# TMR01.net
KiCad netlist of a schematic drawn in EAGLE
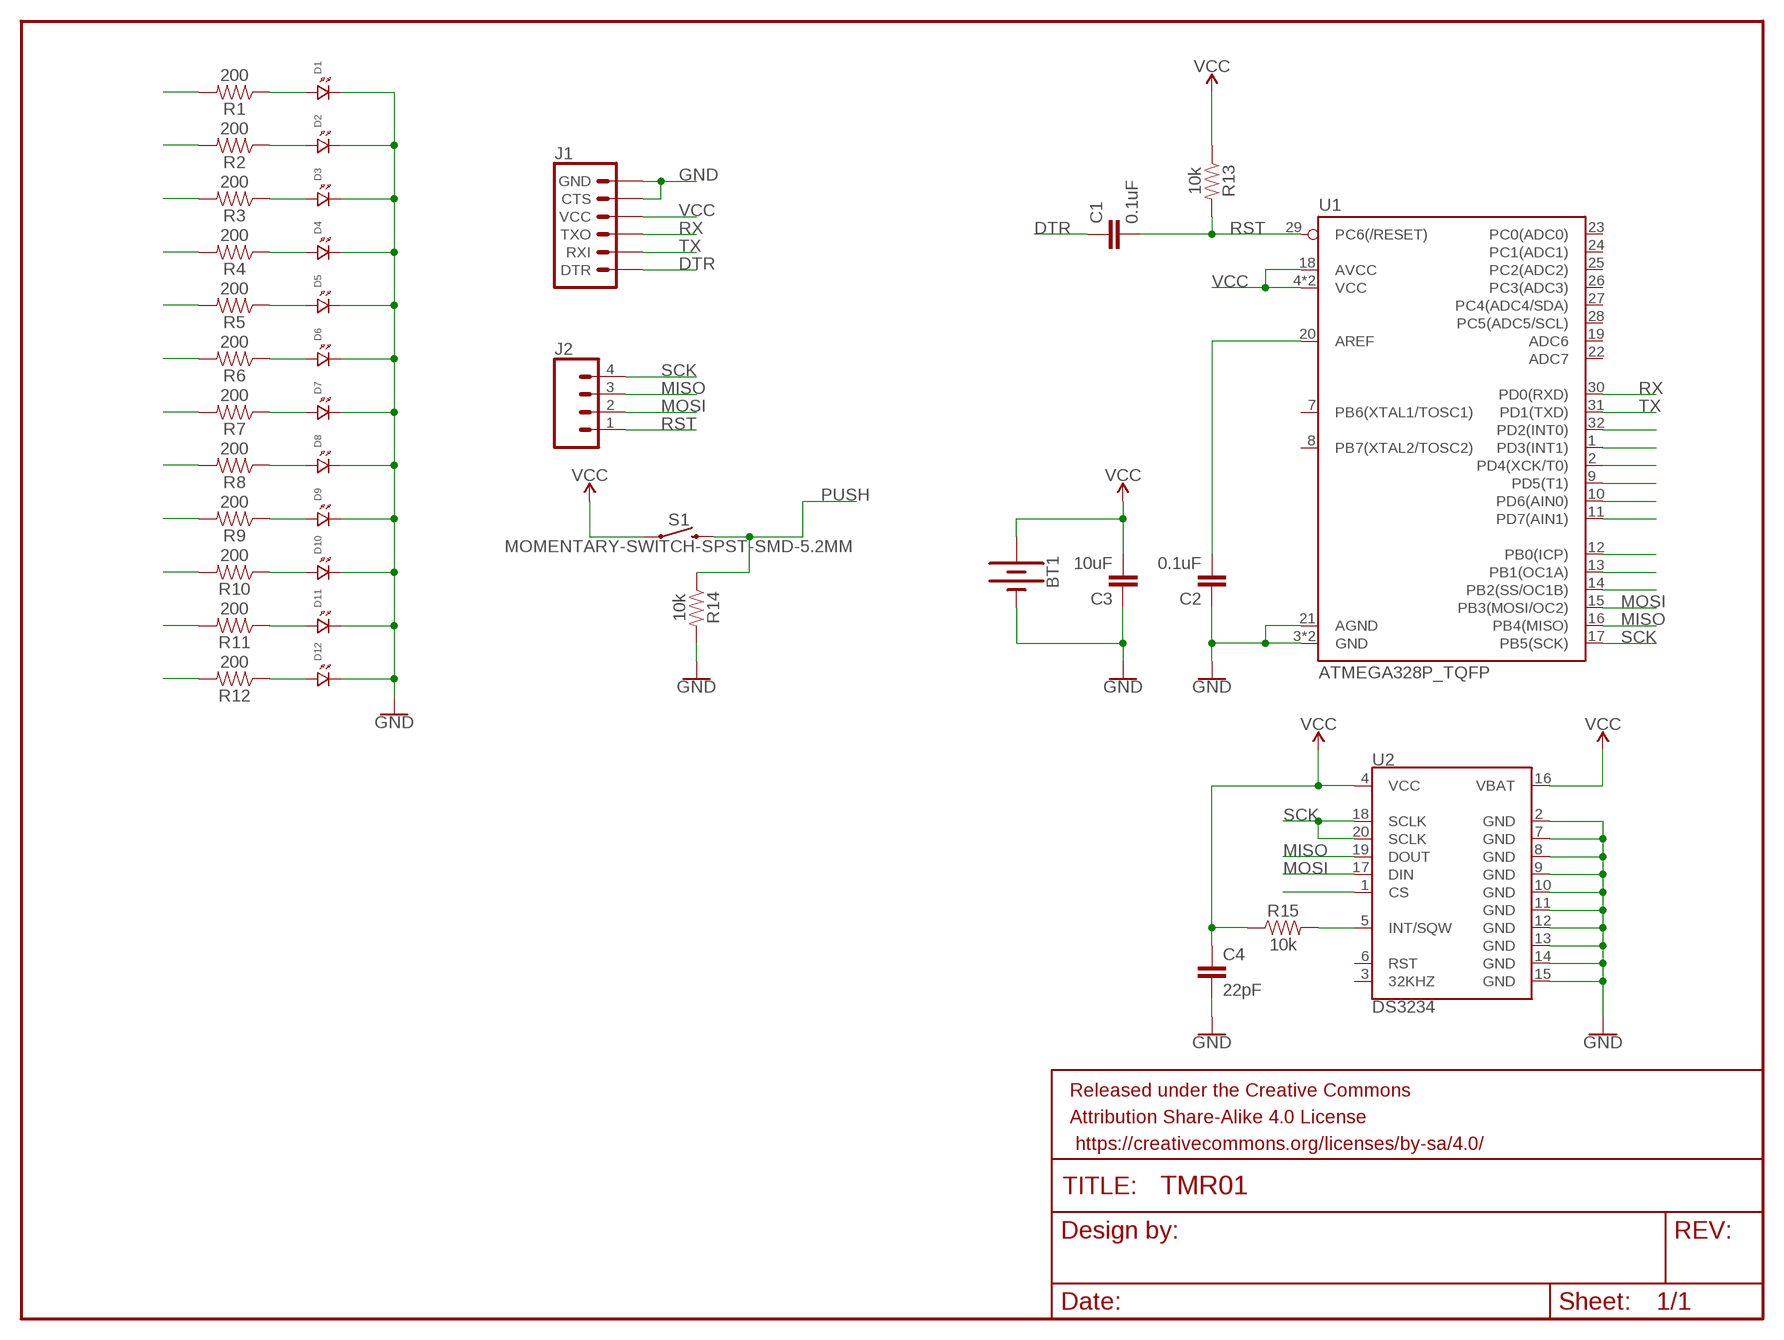
[diagram p0: schematic, sheet 1]

(export (version "E")
  (design (tool "Eeschema 10.0.6"))
  (components
    (comp (ref "BT1")
      (value "BATTERY-20MM_SMD_4LEGS")
      (footprint "eagle-import:BATTCON_20MM_4LEGS")
      (libsource (lib "eagle-import") (part "BATTERY-20MM_SMD_4LEGS"))
    )
    (comp (ref "C1")
      (value "0.1uF")
      (footprint "eagle-import:0402")
      (libsource (lib "eagle-import") (part "0.1UF-0402-16V-10%"))
    )
    (comp (ref "C2")
      (value "0.1uF")
      (footprint "eagle-import:0402")
      (libsource (lib "eagle-import") (part "0.1UF-0402-16V-10%"))
    )
    (comp (ref "C3")
      (value "10uF")
      (footprint "eagle-import:0805")
      (libsource (lib "eagle-import") (part "10UF-0805-10V-10%"))
    )
    (comp (ref "C4")
      (value "22pF")
      (footprint "eagle-import:0402")
      (libsource (lib "eagle-import") (part "CAP_0402"))
    )
    (comp (ref "D1")
      (value "LED.0402")
      (footprint "eagle-import:0402.LED")
      (libsource (lib "eagle-import") (part "LED.0402"))
    )
    (comp (ref "D2")
      (value "LED.0402")
      (footprint "eagle-import:0402.LED")
      (libsource (lib "eagle-import") (part "LED.0402"))
    )
    (comp (ref "D3")
      (value "LED.0402")
      (footprint "eagle-import:0402.LED")
      (libsource (lib "eagle-import") (part "LED.0402"))
    )
    (comp (ref "D4")
      (value "LED.0402")
      (footprint "eagle-import:0402.LED")
      (libsource (lib "eagle-import") (part "LED.0402"))
    )
    (comp (ref "D5")
      (value "LED.0402")
      (footprint "eagle-import:0402.LED")
      (libsource (lib "eagle-import") (part "LED.0402"))
    )
    (comp (ref "D6")
      (value "LED.0402")
      (footprint "eagle-import:0402.LED")
      (libsource (lib "eagle-import") (part "LED.0402"))
    )
    (comp (ref "D7")
      (value "LED.0402")
      (footprint "eagle-import:0402.LED")
      (libsource (lib "eagle-import") (part "LED.0402"))
    )
    (comp (ref "D8")
      (value "LED.0402")
      (footprint "eagle-import:0402.LED")
      (libsource (lib "eagle-import") (part "LED.0402"))
    )
    (comp (ref "D9")
      (value "LED.0402")
      (footprint "eagle-import:0402.LED")
      (libsource (lib "eagle-import") (part "LED.0402"))
    )
    (comp (ref "D10")
      (value "LED.0402")
      (footprint "eagle-import:0402.LED")
      (libsource (lib "eagle-import") (part "LED.0402"))
    )
    (comp (ref "D11")
      (value "LED.0402")
      (footprint "eagle-import:0402.LED")
      (libsource (lib "eagle-import") (part "LED.0402"))
    )
    (comp (ref "D12")
      (value "LED.0402")
      (footprint "eagle-import:0402.LED")
      (libsource (lib "eagle-import") (part "LED.0402"))
    )
    (comp (ref "FRAME1")
      (value "FRAME-LETTER")
      (footprint "eagle-import:CREATIVE_COMMONS")
      (libsource (lib "eagle-import") (part "FRAME-LETTER"))
    )
    (comp (ref "J1")
      (value "6_PIN_SERIAL_TARGET")
      (footprint "eagle-import:1X06")
      (libsource (lib "eagle-import") (part "6_PIN_SERIAL_TARGET"))
    )
    (comp (ref "J2")
      (value "CONN_04")
      (footprint "eagle-import:1X04")
      (libsource (lib "eagle-import") (part "CONN_04"))
    )
    (comp (ref "R1")
      (value "200")
      (footprint "eagle-import:0402")
      (libsource (lib "eagle-import") (part "RESISTOR0402"))
    )
    (comp (ref "R2")
      (value "200")
      (footprint "eagle-import:0402")
      (libsource (lib "eagle-import") (part "RESISTOR0402"))
    )
    (comp (ref "R3")
      (value "200")
      (footprint "eagle-import:0402")
      (libsource (lib "eagle-import") (part "RESISTOR0402"))
    )
    (comp (ref "R4")
      (value "200")
      (footprint "eagle-import:0402")
      (libsource (lib "eagle-import") (part "RESISTOR0402"))
    )
    (comp (ref "R5")
      (value "200")
      (footprint "eagle-import:0402")
      (libsource (lib "eagle-import") (part "RESISTOR0402"))
    )
    (comp (ref "R6")
      (value "200")
      (footprint "eagle-import:0402")
      (libsource (lib "eagle-import") (part "RESISTOR0402"))
    )
    (comp (ref "R7")
      (value "200")
      (footprint "eagle-import:0402")
      (libsource (lib "eagle-import") (part "RESISTOR0402"))
    )
    (comp (ref "R8")
      (value "200")
      (footprint "eagle-import:0402")
      (libsource (lib "eagle-import") (part "RESISTOR0402"))
    )
    (comp (ref "R9")
      (value "200")
      (footprint "eagle-import:0402")
      (libsource (lib "eagle-import") (part "RESISTOR0402"))
    )
    (comp (ref "R10")
      (value "200")
      (footprint "eagle-import:0402")
      (libsource (lib "eagle-import") (part "RESISTOR0402"))
    )
    (comp (ref "R11")
      (value "200")
      (footprint "eagle-import:0402")
      (libsource (lib "eagle-import") (part "RESISTOR0402"))
    )
    (comp (ref "R12")
      (value "200")
      (footprint "eagle-import:0402")
      (libsource (lib "eagle-import") (part "RESISTOR0402"))
    )
    (comp (ref "R13")
      (value "10k")
      (footprint "eagle-import:0402")
      (libsource (lib "eagle-import") (part "RESISTOR0402"))
    )
    (comp (ref "R14")
      (value "10k")
      (footprint "eagle-import:0402")
      (libsource (lib "eagle-import") (part "RESISTOR0402"))
    )
    (comp (ref "R15")
      (value "10k")
      (footprint "eagle-import:0402")
      (libsource (lib "eagle-import") (part "RESISTOR0402"))
    )
    (comp (ref "S1")
      (value "MOMENTARY-SWITCH-SPST-SMD-5.2MM")
      (footprint "eagle-import:TACTILE_SWITCH_SMD_5.2MM")
      (libsource (lib "eagle-import") (part "MOMENTARY-SWITCH-SPST-SMD-5.2MM"))
    )
    (comp (ref "U1")
      (value "ATMEGA328P_TQFP")
      (footprint "eagle-import:TQFP32-08")
      (libsource (lib "eagle-import") (part "ATMEGA328P_TQFP"))
    )
    (comp (ref "U2")
      (value "DS3234")
      (footprint "eagle-import:SO20-0.3")
      (libsource (lib "eagle-import") (part "DS3234"))
    )
  )
  (nets
    (net (code "1") (name "/DTR") (class "Default")
      (node (ref "C1") (pin "1") (pinfunction "1_1") (pintype "passive"))
      (node (ref "J1") (pin "1") (pinfunction "DTR_1") (pintype "passive"))
    )
    (net (code "2") (name "/MISO") (class "Default")
      (node (ref "J2") (pin "3") (pinfunction "3_3") (pintype "passive"))
      (node (ref "U1") (pin "16") (pinfunction "PB4(MISO)_16") (pintype "bidirectional"))
      (node (ref "U2") (pin "19") (pinfunction "DOUT_19") (pintype "bidirectional"))
    )
    (net (code "3") (name "/MOSI") (class "Default")
      (node (ref "J2") (pin "2") (pinfunction "2_2") (pintype "passive"))
      (node (ref "U1") (pin "15") (pinfunction "PB3(MOSI/OC2)_15") (pintype "bidirectional"))
      (node (ref "U2") (pin "17") (pinfunction "DIN_17") (pintype "bidirectional"))
    )
    (net (code "4") (name "/PUSH") (class "Default")
      (node (ref "R14") (pin "1") (pinfunction "1_1") (pintype "passive"))
      (node (ref "S1") (pin "3") (pinfunction "2_3") (pintype "passive"))
    )
    (net (code "5") (name "/RST") (class "Default")
      (node (ref "C1") (pin "2") (pinfunction "2_2") (pintype "passive"))
      (node (ref "J2") (pin "1") (pinfunction "1_1") (pintype "passive"))
      (node (ref "R13") (pin "2") (pinfunction "2_2") (pintype "passive"))
      (node (ref "U1") (pin "29") (pinfunction "PC6(/RESET)_29") (pintype "bidirectional"))
    )
    (net (code "6") (name "/RX") (class "Default")
      (node (ref "J1") (pin "3") (pinfunction "TXO_3") (pintype "passive"))
      (node (ref "U1") (pin "30") (pinfunction "PD0(RXD)_30") (pintype "bidirectional"))
    )
    (net (code "7") (name "/SCK") (class "Default")
      (node (ref "J2") (pin "4") (pinfunction "4_4") (pintype "passive"))
      (node (ref "U1") (pin "17") (pinfunction "PB5(SCK)_17") (pintype "bidirectional"))
      (node (ref "U2") (pin "18") (pinfunction "SCLK_18") (pintype "bidirectional"))
      (node (ref "U2") (pin "20") (pinfunction "SCLK_20") (pintype "bidirectional"))
    )
    (net (code "8") (name "/TX") (class "Default")
      (node (ref "J1") (pin "2") (pinfunction "RXI_2") (pintype "passive"))
      (node (ref "U1") (pin "31") (pinfunction "PD1(TXD)_31") (pintype "bidirectional"))
    )
    (net (code "9") (name "GND") (class "Default")
      (node (ref "BT1") (pin "NEGATIVE") (pinfunction "-_NEGATIVE") (pintype "power_in"))
      (node (ref "C2") (pin "1") (pinfunction "1_1") (pintype "passive"))
      (node (ref "C3") (pin "1") (pinfunction "1_1") (pintype "passive"))
      (node (ref "C4") (pin "2") (pinfunction "2_2") (pintype "passive"))
      (node (ref "D1") (pin "P$2") (pinfunction "2_P$2") (pintype "bidirectional"))
      (node (ref "D10") (pin "P$2") (pinfunction "2_P$2") (pintype "bidirectional"))
      (node (ref "D11") (pin "P$2") (pinfunction "2_P$2") (pintype "bidirectional"))
      (node (ref "D12") (pin "P$2") (pinfunction "2_P$2") (pintype "bidirectional"))
      (node (ref "D2") (pin "P$2") (pinfunction "2_P$2") (pintype "bidirectional"))
      (node (ref "D3") (pin "P$2") (pinfunction "2_P$2") (pintype "bidirectional"))
      (node (ref "D4") (pin "P$2") (pinfunction "2_P$2") (pintype "bidirectional"))
      (node (ref "D5") (pin "P$2") (pinfunction "2_P$2") (pintype "bidirectional"))
      (node (ref "D6") (pin "P$2") (pinfunction "2_P$2") (pintype "bidirectional"))
      (node (ref "D7") (pin "P$2") (pinfunction "2_P$2") (pintype "bidirectional"))
      (node (ref "D8") (pin "P$2") (pinfunction "2_P$2") (pintype "bidirectional"))
      (node (ref "D9") (pin "P$2") (pinfunction "2_P$2") (pintype "bidirectional"))
      (node (ref "J1") (pin "5") (pinfunction "CTS_5") (pintype "passive"))
      (node (ref "J1") (pin "6") (pinfunction "GND_6") (pintype "passive"))
      (node (ref "R14") (pin "2") (pinfunction "2_2") (pintype "passive"))
      (node (ref "U1") (pin "21") (pinfunction "AGND_21") (pintype "bidirectional"))
      (node (ref "U1") (pin "3") (pinfunction "GND_3") (pintype "bidirectional"))
      (node (ref "U1") (pin "5") (pinfunction "GND_5") (pintype "bidirectional"))
      (node (ref "U2") (pin "10") (pinfunction "GND_10") (pintype "bidirectional"))
      (node (ref "U2") (pin "11") (pinfunction "GND_11") (pintype "bidirectional"))
      (node (ref "U2") (pin "12") (pinfunction "GND_12") (pintype "bidirectional"))
      (node (ref "U2") (pin "13") (pinfunction "GND_13") (pintype "bidirectional"))
      (node (ref "U2") (pin "14") (pinfunction "GND_14") (pintype "bidirectional"))
      (node (ref "U2") (pin "15") (pinfunction "GND_15") (pintype "bidirectional"))
      (node (ref "U2") (pin "2") (pinfunction "GND_2") (pintype "bidirectional"))
      (node (ref "U2") (pin "7") (pinfunction "GND_7") (pintype "bidirectional"))
      (node (ref "U2") (pin "8") (pinfunction "GND_8") (pintype "bidirectional"))
      (node (ref "U2") (pin "9") (pinfunction "GND_9") (pintype "bidirectional"))
    )
    (net (code "10") (name "Net-(D1-1)") (class "Default")
      (node (ref "D1") (pin "P$1") (pinfunction "1_P$1") (pintype "bidirectional"))
      (node (ref "R1") (pin "1") (pinfunction "1_1") (pintype "passive"))
    )
    (net (code "11") (name "Net-(D2-1)") (class "Default")
      (node (ref "D2") (pin "P$1") (pinfunction "1_P$1") (pintype "bidirectional"))
      (node (ref "R2") (pin "1") (pinfunction "1_1") (pintype "passive"))
    )
    (net (code "12") (name "Net-(D3-1)") (class "Default")
      (node (ref "D3") (pin "P$1") (pinfunction "1_P$1") (pintype "bidirectional"))
      (node (ref "R3") (pin "1") (pinfunction "1_1") (pintype "passive"))
    )
    (net (code "13") (name "Net-(D4-1)") (class "Default")
      (node (ref "D4") (pin "P$1") (pinfunction "1_P$1") (pintype "bidirectional"))
      (node (ref "R4") (pin "1") (pinfunction "1_1") (pintype "passive"))
    )
    (net (code "14") (name "Net-(D5-1)") (class "Default")
      (node (ref "D5") (pin "P$1") (pinfunction "1_P$1") (pintype "bidirectional"))
      (node (ref "R5") (pin "1") (pinfunction "1_1") (pintype "passive"))
    )
    (net (code "15") (name "Net-(D6-1)") (class "Default")
      (node (ref "D6") (pin "P$1") (pinfunction "1_P$1") (pintype "bidirectional"))
      (node (ref "R6") (pin "1") (pinfunction "1_1") (pintype "passive"))
    )
    (net (code "16") (name "Net-(D7-1)") (class "Default")
      (node (ref "D7") (pin "P$1") (pinfunction "1_P$1") (pintype "bidirectional"))
      (node (ref "R7") (pin "1") (pinfunction "1_1") (pintype "passive"))
    )
    (net (code "17") (name "Net-(D8-1)") (class "Default")
      (node (ref "D8") (pin "P$1") (pinfunction "1_P$1") (pintype "bidirectional"))
      (node (ref "R8") (pin "1") (pinfunction "1_1") (pintype "passive"))
    )
    (net (code "18") (name "Net-(D9-1)") (class "Default")
      (node (ref "D9") (pin "P$1") (pinfunction "1_P$1") (pintype "bidirectional"))
      (node (ref "R9") (pin "1") (pinfunction "1_1") (pintype "passive"))
    )
    (net (code "19") (name "Net-(D10-1)") (class "Default")
      (node (ref "D10") (pin "P$1") (pinfunction "1_P$1") (pintype "bidirectional"))
      (node (ref "R10") (pin "1") (pinfunction "1_1") (pintype "passive"))
    )
    (net (code "20") (name "Net-(D11-1)") (class "Default")
      (node (ref "D11") (pin "P$1") (pinfunction "1_P$1") (pintype "bidirectional"))
      (node (ref "R11") (pin "1") (pinfunction "1_1") (pintype "passive"))
    )
    (net (code "21") (name "Net-(D12-1)") (class "Default")
      (node (ref "D12") (pin "P$1") (pinfunction "1_P$1") (pintype "bidirectional"))
      (node (ref "R12") (pin "1") (pinfunction "1_1") (pintype "passive"))
    )
    (net (code "22") (name "Net-(U1-AREF)") (class "Default")
      (node (ref "C2") (pin "2") (pinfunction "2_2") (pintype "passive"))
      (node (ref "U1") (pin "20") (pinfunction "AREF_20") (pintype "bidirectional"))
    )
    (net (code "23") (name "Net-(U2-INT{slash}SQW)") (class "Default")
      (node (ref "R15") (pin "2") (pinfunction "2_2") (pintype "passive"))
      (node (ref "U2") (pin "5") (pinfunction "INT/SQW_5") (pintype "bidirectional"))
    )
    (net (code "24") (name "VCC") (class "Default")
      (node (ref "BT1") (pin "POSITIVE@1") (pinfunction "+_POSITIVE@1") (pintype "power_in"))
      (node (ref "BT1") (pin "POSITIVE@2") (pinfunction "+_POSITIVE@2") (pintype "power_in"))
      (node (ref "BT1") (pin "POSITIVE@3") (pinfunction "+_POSITIVE@3") (pintype "power_in"))
      (node (ref "BT1") (pin "POSITIVE@4") (pinfunction "+_POSITIVE@4") (pintype "power_in"))
      (node (ref "C3") (pin "2") (pinfunction "2_2") (pintype "passive"))
      (node (ref "C4") (pin "1") (pinfunction "1_1") (pintype "passive"))
      (node (ref "J1") (pin "4") (pinfunction "VCC_4") (pintype "passive"))
      (node (ref "R13") (pin "1") (pinfunction "1_1") (pintype "passive"))
      (node (ref "R15") (pin "1") (pinfunction "1_1") (pintype "passive"))
      (node (ref "S1") (pin "1") (pinfunction "1_1") (pintype "passive"))
      (node (ref "U1") (pin "18") (pinfunction "AVCC_18") (pintype "bidirectional"))
      (node (ref "U1") (pin "4") (pinfunction "VCC_4") (pintype "bidirectional"))
      (node (ref "U1") (pin "6") (pinfunction "VCC_6") (pintype "bidirectional"))
      (node (ref "U2") (pin "16") (pinfunction "VBAT_16") (pintype "bidirectional"))
      (node (ref "U2") (pin "4") (pinfunction "VCC_4") (pintype "bidirectional"))
    )
    (net (code "25") (name "unconnected-(R1-Pad2)") (class "Default")
      (node (ref "R1") (pin "2") (pinfunction "2_2") (pintype "passive"))
    )
    (net (code "26") (name "unconnected-(R2-Pad2)") (class "Default")
      (node (ref "R2") (pin "2") (pinfunction "2_2") (pintype "passive"))
    )
    (net (code "27") (name "unconnected-(R3-Pad2)") (class "Default")
      (node (ref "R3") (pin "2") (pinfunction "2_2") (pintype "passive"))
    )
    (net (code "28") (name "unconnected-(R4-Pad2)") (class "Default")
      (node (ref "R4") (pin "2") (pinfunction "2_2") (pintype "passive"))
    )
    (net (code "29") (name "unconnected-(R5-Pad2)") (class "Default")
      (node (ref "R5") (pin "2") (pinfunction "2_2") (pintype "passive"))
    )
    (net (code "30") (name "unconnected-(R6-Pad2)") (class "Default")
      (node (ref "R6") (pin "2") (pinfunction "2_2") (pintype "passive"))
    )
    (net (code "31") (name "unconnected-(R7-Pad2)") (class "Default")
      (node (ref "R7") (pin "2") (pinfunction "2_2") (pintype "passive"))
    )
    (net (code "32") (name "unconnected-(R8-Pad2)") (class "Default")
      (node (ref "R8") (pin "2") (pinfunction "2_2") (pintype "passive"))
    )
    (net (code "33") (name "unconnected-(R9-Pad2)") (class "Default")
      (node (ref "R9") (pin "2") (pinfunction "2_2") (pintype "passive"))
    )
    (net (code "34") (name "unconnected-(R10-Pad2)") (class "Default")
      (node (ref "R10") (pin "2") (pinfunction "2_2") (pintype "passive"))
    )
    (net (code "35") (name "unconnected-(R11-Pad2)") (class "Default")
      (node (ref "R11") (pin "2") (pinfunction "2_2") (pintype "passive"))
    )
    (net (code "36") (name "unconnected-(R12-Pad2)") (class "Default")
      (node (ref "R12") (pin "2") (pinfunction "2_2") (pintype "passive"))
    )
    (net (code "37") (name "unconnected-(U1-ADC6-Pad19)") (class "Default")
      (node (ref "U1") (pin "19") (pinfunction "ADC6_19") (pintype "bidirectional"))
    )
    (net (code "38") (name "unconnected-(U1-ADC7-Pad22)") (class "Default")
      (node (ref "U1") (pin "22") (pinfunction "ADC7_22") (pintype "bidirectional"))
    )
    (net (code "39") (name "unconnected-(U1-PB0(ICP)-Pad12)") (class "Default")
      (node (ref "U1") (pin "12") (pinfunction "PB0(ICP)_12") (pintype "bidirectional"))
    )
    (net (code "40") (name "unconnected-(U1-PB1(OC1A)-Pad13)") (class "Default")
      (node (ref "U1") (pin "13") (pinfunction "PB1(OC1A)_13") (pintype "bidirectional"))
    )
    (net (code "41") (name "unconnected-(U1-PB2(SS{slash}OC1B)-Pad14)") (class "Default")
      (node (ref "U1") (pin "14") (pinfunction "PB2(SS/OC1B)_14") (pintype "bidirectional"))
    )
    (net (code "42") (name "unconnected-(U1-PB6(XTAL1{slash}TOSC1)-Pad7)") (class "Default")
      (node (ref "U1") (pin "7") (pinfunction "PB6(XTAL1/TOSC1)_7") (pintype "bidirectional"))
    )
    (net (code "43") (name "unconnected-(U1-PB7(XTAL2{slash}TOSC2)-Pad8)") (class "Default")
      (node (ref "U1") (pin "8") (pinfunction "PB7(XTAL2/TOSC2)_8") (pintype "bidirectional"))
    )
    (net (code "44") (name "unconnected-(U1-PC0(ADC0)-Pad23)") (class "Default")
      (node (ref "U1") (pin "23") (pinfunction "PC0(ADC0)_23") (pintype "bidirectional"))
    )
    (net (code "45") (name "unconnected-(U1-PC1(ADC1)-Pad24)") (class "Default")
      (node (ref "U1") (pin "24") (pinfunction "PC1(ADC1)_24") (pintype "bidirectional"))
    )
    (net (code "46") (name "unconnected-(U1-PC2(ADC2)-Pad25)") (class "Default")
      (node (ref "U1") (pin "25") (pinfunction "PC2(ADC2)_25") (pintype "bidirectional"))
    )
    (net (code "47") (name "unconnected-(U1-PC3(ADC3)-Pad26)") (class "Default")
      (node (ref "U1") (pin "26") (pinfunction "PC3(ADC3)_26") (pintype "bidirectional"))
    )
    (net (code "48") (name "unconnected-(U1-PC4(ADC4{slash}SDA)-Pad27)") (class "Default")
      (node (ref "U1") (pin "27") (pinfunction "PC4(ADC4/SDA)_27") (pintype "bidirectional"))
    )
    (net (code "49") (name "unconnected-(U1-PC5(ADC5{slash}SCL)-Pad28)") (class "Default")
      (node (ref "U1") (pin "28") (pinfunction "PC5(ADC5/SCL)_28") (pintype "bidirectional"))
    )
    (net (code "50") (name "unconnected-(U1-PD2(INT0)-Pad32)") (class "Default")
      (node (ref "U1") (pin "32") (pinfunction "PD2(INT0)_32") (pintype "bidirectional"))
    )
    (net (code "51") (name "unconnected-(U1-PD3(INT1)-Pad1)") (class "Default")
      (node (ref "U1") (pin "1") (pinfunction "PD3(INT1)_1") (pintype "bidirectional"))
    )
    (net (code "52") (name "unconnected-(U1-PD4(XCK{slash}T0)-Pad2)") (class "Default")
      (node (ref "U1") (pin "2") (pinfunction "PD4(XCK/T0)_2") (pintype "bidirectional"))
    )
    (net (code "53") (name "unconnected-(U1-PD5(T1)-Pad9)") (class "Default")
      (node (ref "U1") (pin "9") (pinfunction "PD5(T1)_9") (pintype "bidirectional"))
    )
    (net (code "54") (name "unconnected-(U1-PD6(AIN0)-Pad10)") (class "Default")
      (node (ref "U1") (pin "10") (pinfunction "PD6(AIN0)_10") (pintype "bidirectional"))
    )
    (net (code "55") (name "unconnected-(U1-PD7(AIN1)-Pad11)") (class "Default")
      (node (ref "U1") (pin "11") (pinfunction "PD7(AIN1)_11") (pintype "bidirectional"))
    )
    (net (code "56") (name "unconnected-(U2-32KHZ-Pad3)") (class "Default")
      (node (ref "U2") (pin "3") (pinfunction "32KHZ_3") (pintype "bidirectional"))
    )
    (net (code "57") (name "unconnected-(U2-CS-Pad1)") (class "Default")
      (node (ref "U2") (pin "1") (pinfunction "CS_1") (pintype "bidirectional"))
    )
    (net (code "58") (name "unconnected-(U2-RST-Pad6)") (class "Default")
      (node (ref "U2") (pin "6") (pinfunction "RST_6") (pintype "bidirectional"))
    )
  )
)
